# PIRSN_v2.net
KiCad netlist of a schematic drawn in EAGLE
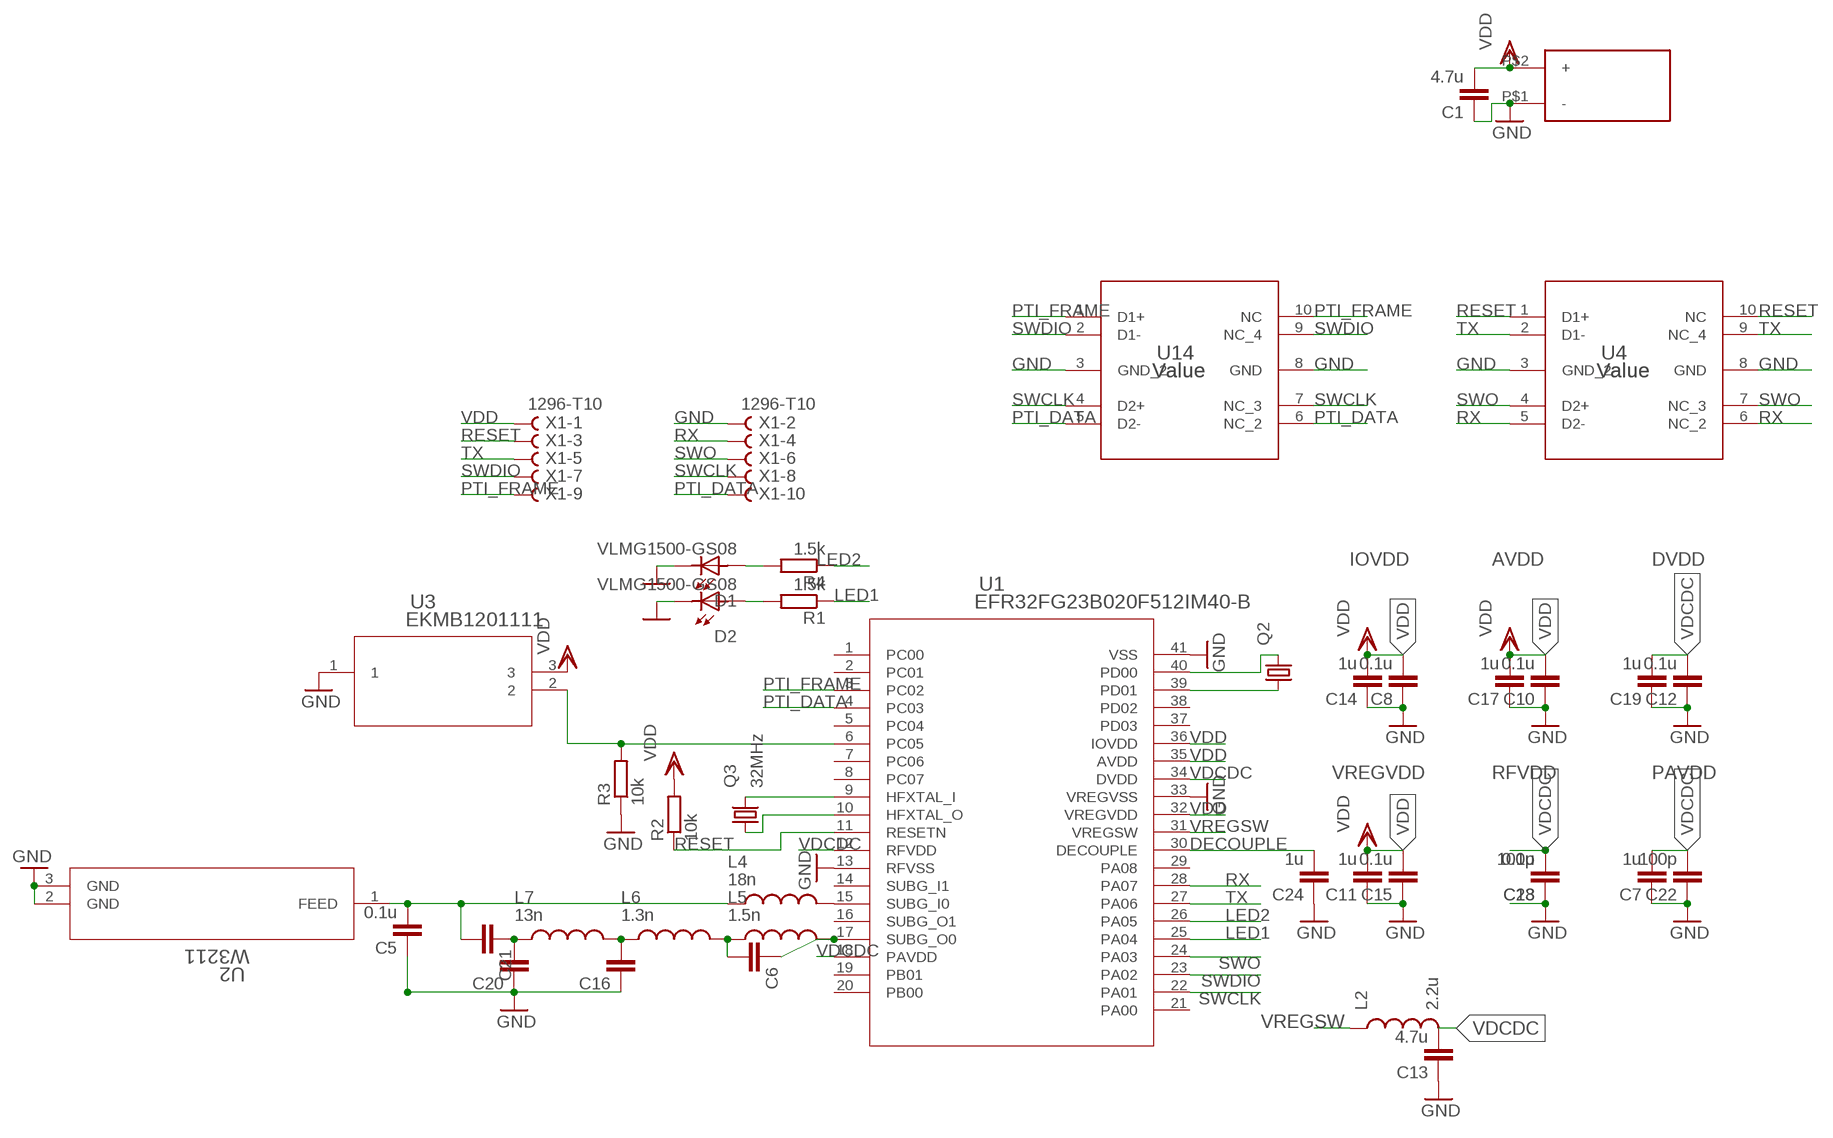
[diagram p0: schematic, sheet 1]

(export (version "E")
  (design (tool "Eeschema 10.0.6"))
  (components
    (comp (ref "C1")
      (value "4.7u")
      (footprint "eagle-import:C0603R")
      (libsource (lib "eagle-import") (part "CC0603R"))
    )
    (comp (ref "C5")
      (value "0.1u")
      (footprint "eagle-import:C0402")
      (libsource (lib "eagle-import") (part "CC0402"))
    )
    (comp (ref "C6")
      (value "1.9p")
      (footprint "eagle-import:C0402")
      (libsource (lib "eagle-import") (part "CC0402"))
    )
    (comp (ref "C7")
      (value "1u")
      (footprint "eagle-import:C0402")
      (libsource (lib "eagle-import") (part "CC0402"))
    )
    (comp (ref "C8")
      (value "0.1u")
      (footprint "eagle-import:C0402")
      (libsource (lib "eagle-import") (part "CC0402"))
    )
    (comp (ref "C10")
      (value "0.1u")
      (footprint "eagle-import:C0402")
      (libsource (lib "eagle-import") (part "CC0402"))
    )
    (comp (ref "C11")
      (value "1u")
      (footprint "eagle-import:C0402")
      (libsource (lib "eagle-import") (part "CC0402"))
    )
    (comp (ref "C12")
      (value "0.1u")
      (footprint "eagle-import:C0402")
      (libsource (lib "eagle-import") (part "CC0402"))
    )
    (comp (ref "C13")
      (value "4.7u")
      (footprint "eagle-import:C0603R")
      (libsource (lib "eagle-import") (part "CC0603R"))
    )
    (comp (ref "C14")
      (value "1u")
      (footprint "eagle-import:C0402")
      (libsource (lib "eagle-import") (part "CC0402"))
    )
    (comp (ref "C15")
      (value "0.1u")
      (footprint "eagle-import:C0402")
      (libsource (lib "eagle-import") (part "CC0402"))
    )
    (comp (ref "C16")
      (value "7.2p")
      (footprint "eagle-import:C0402")
      (libsource (lib "eagle-import") (part "CC0402"))
    )
    (comp (ref "C17")
      (value "1u")
      (footprint "eagle-import:C0402")
      (libsource (lib "eagle-import") (part "CC0402"))
    )
    (comp (ref "C18")
      (value "0.1u")
      (footprint "eagle-import:C0402")
      (libsource (lib "eagle-import") (part "CC0402"))
    )
    (comp (ref "C19")
      (value "1u")
      (footprint "eagle-import:C0402")
      (libsource (lib "eagle-import") (part "CC0402"))
    )
    (comp (ref "C20")
      (value "1.3p")
      (footprint "eagle-import:C0402")
      (libsource (lib "eagle-import") (part "CC0402"))
    )
    (comp (ref "C21")
      (value "220p")
      (footprint "eagle-import:C0402")
      (libsource (lib "eagle-import") (part "CC0402"))
    )
    (comp (ref "C22")
      (value "100p")
      (footprint "eagle-import:C0402")
      (libsource (lib "eagle-import") (part "CC0402"))
    )
    (comp (ref "C23")
      (value "100p")
      (footprint "eagle-import:C0402")
      (libsource (lib "eagle-import") (part "CC0402"))
    )
    (comp (ref "C24")
      (value "1u")
      (footprint "eagle-import:C0402")
      (libsource (lib "eagle-import") (part "CC0402"))
    )
    (comp (ref "D1")
      (value "VLMG1500-GS08")
      (footprint "eagle-import:LEDC1005X35N")
      (fields (field (name "MF") "Vishay"))
      (libsource (lib "eagle-import") (part "VLMG1500-GS08"))
    )
    (comp (ref "D2")
      (value "VLMG1500-GS08")
      (footprint "eagle-import:LEDC1005X35N")
      (fields (field (name "MF") "Vishay"))
      (libsource (lib "eagle-import") (part "VLMG1500-GS08"))
    )
    (comp (ref "L2")
      (value "2.2u")
      (footprint "eagle-import:L0603")
      (libsource (lib "eagle-import") (part "INDUCTOR"))
    )
    (comp (ref "L4")
      (value "18n")
      (footprint "eagle-import:INDC0402X26N")
      (fields (field (name "MF") "TDK") (field (name "MP") "MHQ0402P7N5JT000"))
      (libsource (lib "eagle-import") (part "MHQ0402P7N5JT000"))
    )
    (comp (ref "L5")
      (value "1.5n")
      (footprint "eagle-import:INDC0402X26N")
      (fields (field (name "MF") "TDK") (field (name "MP") "MHQ0402P7N5JT000"))
      (libsource (lib "eagle-import") (part "MHQ0402P7N5JT000"))
    )
    (comp (ref "L6")
      (value "1.3n")
      (footprint "eagle-import:INDC0402X26N")
      (fields (field (name "MF") "TDK") (field (name "MP") "MHQ0402P7N5JT000"))
      (libsource (lib "eagle-import") (part "MHQ0402P7N5JT000"))
    )
    (comp (ref "L7")
      (value "13n")
      (footprint "eagle-import:INDC0402X26N")
      (fields (field (name "MF") "TDK") (field (name "MP") "MHQ0402P7N5JT000"))
      (libsource (lib "eagle-import") (part "MHQ0402P7N5JT000"))
    )
    (comp (ref "Q2")
      (value "KX-327-RT")
      (footprint "eagle-import:2.0X1.2")
      (libsource (lib "eagle-import") (part "KX-327-RT"))
    )
    (comp (ref "Q3")
      (value "32MHz")
      (footprint "eagle-import:2.0X1.6_KX-5")
      (libsource (lib "eagle-import") (part "KX-5"))
    )
    (comp (ref "R1")
      (value "1.5k")
      (footprint "eagle-import:R0402")
      (libsource (lib "eagle-import") (part "RR0402"))
    )
    (comp (ref "R2")
      (value "10k")
      (footprint "eagle-import:R0402")
      (libsource (lib "eagle-import") (part "RR0402"))
    )
    (comp (ref "R3")
      (value "10k")
      (footprint "eagle-import:R0402")
      (libsource (lib "eagle-import") (part "RR0402"))
    )
    (comp (ref "R4")
      (value "1.5k")
      (footprint "eagle-import:R0402")
      (libsource (lib "eagle-import") (part "RR0402"))
    )
    (comp (ref "U$2")
      (value "BS-24R")
      (footprint "eagle-import:BS-24")
      (libsource (lib "eagle-import") (part "BS-24R"))
    )
    (comp (ref "U1")
      (value "EFR32FG23B020F512IM40-B")
      (footprint "eagle-import:QFN_40_SIL")
      (fields (field (name "COPYRIGHT") "Copyright (C) 2022 Ultra Librarian. All rights reserved."))
      (libsource (lib "eagle-import") (part "EFR32FG23B020F512IM40-B"))
    )
    (comp (ref "U2")
      (value "W3211")
      (footprint "eagle-import:CHIP_3211_PUL")
      (fields (field (name "COPYRIGHT") "Copyright (C) 2022 Ultra Librarian. All rights reserved."))
      (libsource (lib "eagle-import") (part "W3211"))
    )
    (comp (ref "U3")
      (value "EKMB1201111")
      (footprint "eagle-import:SENSOR_B1201111_PAN")
      (fields (field (name "COPYRIGHT") "Copyright (C) 2022 Ultra Librarian. All rights reserved."))
      (libsource (lib "eagle-import") (part "EKMB1201111"))
    )
    (comp (ref "U4")
      (value "Value")
      (footprint "eagle-import:DQA0010A")
      (fields (field (name "MANUFACTURER") "Texas Instruments") (field (name "PARTNUMBER") "ESD204DQAR"))
      (libsource (lib "eagle-import") (part "ESD204DQAR"))
    )
    (comp (ref "U14")
      (value "Value")
      (footprint "eagle-import:DQA0010A")
      (fields (field (name "MANUFACTURER") "Texas Instruments") (field (name "PARTNUMBER") "ESD204DQAR"))
      (libsource (lib "eagle-import") (part "ESD204DQAR"))
    )
    (comp (ref "X1")
      (value "1296-T10")
      (footprint "eagle-import:1296-10")
      (libsource (lib "eagle-import") (part "1296-T10"))
    )
  )
  (nets
    (net (code "1") (name "/DECOUPLE") (class "Default")
      (node (ref "C24") (pin "2") (pinfunction "2_2") (pintype "passive"))
      (node (ref "U1") (pin "30") (pinfunction "DECOUPLE_30") (pintype "passive"))
    )
    (net (code "2") (name "/LED1") (class "Default")
      (node (ref "R1") (pin "1") (pinfunction "1_1") (pintype "passive"))
      (node (ref "U1") (pin "25") (pinfunction "PA04_25") (pintype "bidirectional"))
    )
    (net (code "3") (name "/LED2") (class "Default")
      (node (ref "R4") (pin "1") (pinfunction "1_1") (pintype "passive"))
      (node (ref "U1") (pin "26") (pinfunction "PA05_26") (pintype "bidirectional"))
    )
    (net (code "4") (name "/PTI_DATA") (class "Default")
      (node (ref "U1") (pin "4") (pinfunction "PC03_4") (pintype "bidirectional"))
      (node (ref "U14") (pin "5") (pinfunction "D2-_5") (pintype "bidirectional"))
      (node (ref "U14") (pin "6") (pinfunction "NC_2_6") (pintype "passive"))
      (node (ref "X1") (pin "10") (pinfunction "B_10") (pintype "passive"))
    )
    (net (code "5") (name "/PTI_FRAME") (class "Default")
      (node (ref "U1") (pin "3") (pinfunction "PC02_3") (pintype "bidirectional"))
      (node (ref "U14") (pin "1") (pinfunction "D1+_1") (pintype "bidirectional"))
      (node (ref "U14") (pin "10") (pinfunction "NC_10") (pintype "passive"))
      (node (ref "X1") (pin "9") (pinfunction "B_9") (pintype "passive"))
    )
    (net (code "6") (name "/RESET") (class "Default")
      (node (ref "R2") (pin "1") (pinfunction "1_1") (pintype "passive"))
      (node (ref "U1") (pin "11") (pinfunction "RESETN_11") (pintype "input"))
      (node (ref "U4") (pin "1") (pinfunction "D1+_1") (pintype "bidirectional"))
      (node (ref "U4") (pin "10") (pinfunction "NC_10") (pintype "passive"))
      (node (ref "X1") (pin "3") (pinfunction "B_3") (pintype "passive"))
    )
    (net (code "7") (name "/RX") (class "Default")
      (node (ref "U1") (pin "28") (pinfunction "PA07_28") (pintype "bidirectional"))
      (node (ref "U4") (pin "5") (pinfunction "D2-_5") (pintype "bidirectional"))
      (node (ref "U4") (pin "6") (pinfunction "NC_2_6") (pintype "passive"))
      (node (ref "X1") (pin "4") (pinfunction "B_4") (pintype "passive"))
    )
    (net (code "8") (name "/SWCLK") (class "Default")
      (node (ref "U1") (pin "22") (pinfunction "PA01_22") (pintype "bidirectional"))
      (node (ref "U14") (pin "4") (pinfunction "D2+_4") (pintype "bidirectional"))
      (node (ref "U14") (pin "7") (pinfunction "NC_3_7") (pintype "passive"))
      (node (ref "X1") (pin "8") (pinfunction "B_8") (pintype "passive"))
    )
    (net (code "9") (name "/SWDIO") (class "Default")
      (node (ref "U1") (pin "23") (pinfunction "PA02_23") (pintype "bidirectional"))
      (node (ref "U14") (pin "2") (pinfunction "D1-_2") (pintype "bidirectional"))
      (node (ref "U14") (pin "9") (pinfunction "NC_4_9") (pintype "passive"))
      (node (ref "X1") (pin "7") (pinfunction "B_7") (pintype "passive"))
    )
    (net (code "10") (name "/SWO") (class "Default")
      (node (ref "U1") (pin "24") (pinfunction "PA03_24") (pintype "bidirectional"))
      (node (ref "U4") (pin "4") (pinfunction "D2+_4") (pintype "bidirectional"))
      (node (ref "U4") (pin "7") (pinfunction "NC_3_7") (pintype "passive"))
      (node (ref "X1") (pin "6") (pinfunction "B_6") (pintype "passive"))
    )
    (net (code "11") (name "/TX") (class "Default")
      (node (ref "U1") (pin "27") (pinfunction "PA06_27") (pintype "bidirectional"))
      (node (ref "U4") (pin "2") (pinfunction "D1-_2") (pintype "bidirectional"))
      (node (ref "U4") (pin "9") (pinfunction "NC_4_9") (pintype "passive"))
      (node (ref "X1") (pin "5") (pinfunction "B_5") (pintype "passive"))
    )
    (net (code "12") (name "/VREGSW") (class "Default")
      (node (ref "L2") (pin "1") (pinfunction "1_1") (pintype "passive"))
      (node (ref "U1") (pin "31") (pinfunction "VREGSW_31") (pintype "power_in"))
    )
    (net (code "13") (name "GND") (class "Default")
      (node (ref "C1") (pin "1") (pinfunction "1_1") (pintype "passive"))
      (node (ref "C10") (pin "1") (pinfunction "1_1") (pintype "passive"))
      (node (ref "C11") (pin "1") (pinfunction "1_1") (pintype "passive"))
      (node (ref "C12") (pin "1") (pinfunction "1_1") (pintype "passive"))
      (node (ref "C13") (pin "1") (pinfunction "1_1") (pintype "passive"))
      (node (ref "C14") (pin "1") (pinfunction "1_1") (pintype "passive"))
      (node (ref "C15") (pin "1") (pinfunction "1_1") (pintype "passive"))
      (node (ref "C16") (pin "1") (pinfunction "1_1") (pintype "passive"))
      (node (ref "C17") (pin "1") (pinfunction "1_1") (pintype "passive"))
      (node (ref "C18") (pin "1") (pinfunction "1_1") (pintype "passive"))
      (node (ref "C19") (pin "1") (pinfunction "1_1") (pintype "passive"))
      (node (ref "C20") (pin "1") (pinfunction "1_1") (pintype "passive"))
      (node (ref "C22") (pin "1") (pinfunction "1_1") (pintype "passive"))
      (node (ref "C23") (pin "1") (pinfunction "1_1") (pintype "passive"))
      (node (ref "C24") (pin "1") (pinfunction "1_1") (pintype "passive"))
      (node (ref "C5") (pin "1") (pinfunction "1_1") (pintype "passive"))
      (node (ref "C7") (pin "1") (pinfunction "1_1") (pintype "passive"))
      (node (ref "C8") (pin "1") (pinfunction "1_1") (pintype "passive"))
      (node (ref "D1") (pin "2") (pinfunction "2_2") (pintype "passive"))
      (node (ref "D2") (pin "2") (pinfunction "2_2") (pintype "passive"))
      (node (ref "R3") (pin "1") (pinfunction "1_1") (pintype "passive"))
      (node (ref "U$2") (pin "P$1") (pinfunction "-_P$1") (pintype "bidirectional"))
      (node (ref "U1") (pin "13") (pinfunction "RFVSS_13") (pintype "power_in"))
      (node (ref "U1") (pin "33") (pinfunction "VREGVSS_33") (pintype "power_in"))
      (node (ref "U1") (pin "41") (pinfunction "VSS_41") (pintype "power_in"))
      (node (ref "U14") (pin "3") (pinfunction "GND_2_3") (pintype "power_in"))
      (node (ref "U14") (pin "8") (pinfunction "GND_8") (pintype "power_in"))
      (node (ref "U2") (pin "2") (pinfunction "GND_2") (pintype "passive"))
      (node (ref "U2") (pin "3") (pinfunction "GND_3") (pintype "passive"))
      (node (ref "U3") (pin "1") (pinfunction "1_1") (pintype "passive"))
      (node (ref "U4") (pin "3") (pinfunction "GND_2_3") (pintype "power_in"))
      (node (ref "U4") (pin "8") (pinfunction "GND_8") (pintype "power_in"))
      (node (ref "X1") (pin "2") (pinfunction "B_2") (pintype "passive"))
    )
    (net (code "14") (name "Net-(C6-Pad2)") (class "Default")
      (node (ref "C6") (pin "2") (pinfunction "2_2") (pintype "passive"))
      (node (ref "L5") (pin "1") (pinfunction "1_1") (pintype "passive"))
      (node (ref "L6") (pin "2") (pinfunction "2_2") (pintype "passive"))
    )
    (net (code "15") (name "Net-(C16-Pad2)") (class "Default")
      (node (ref "C16") (pin "2") (pinfunction "2_2") (pintype "passive"))
      (node (ref "L6") (pin "1") (pinfunction "1_1") (pintype "passive"))
      (node (ref "L7") (pin "2") (pinfunction "2_2") (pintype "passive"))
    )
    (net (code "16") (name "Net-(C20-Pad2)") (class "Default")
      (node (ref "C20") (pin "2") (pinfunction "2_2") (pintype "passive"))
      (node (ref "C21") (pin "1") (pinfunction "1_1") (pintype "passive"))
      (node (ref "L7") (pin "1") (pinfunction "1_1") (pintype "passive"))
    )
    (net (code "17") (name "Net-(D1-Pad1)") (class "Default")
      (node (ref "D1") (pin "1") (pinfunction "1_1") (pintype "passive"))
      (node (ref "R4") (pin "2") (pinfunction "2_2") (pintype "passive"))
    )
    (net (code "18") (name "Net-(D2-Pad1)") (class "Default")
      (node (ref "D2") (pin "1") (pinfunction "1_1") (pintype "passive"))
      (node (ref "R1") (pin "2") (pinfunction "2_2") (pintype "passive"))
    )
    (net (code "19") (name "Net-(Q3-2)") (class "Default")
      (node (ref "Q3") (pin "3") (pinfunction "2_3") (pintype "passive"))
      (node (ref "U1") (pin "9") (pinfunction "HFXTAL_I_9") (pintype "input"))
    )
    (net (code "20") (name "Net-(U1-HFXTAL_O)") (class "Default")
      (node (ref "Q3") (pin "1") (pinfunction "1_1") (pintype "passive"))
      (node (ref "U1") (pin "10") (pinfunction "HFXTAL_O_10") (pintype "output"))
    )
    (net (code "21") (name "Net-(U1-PC05)") (class "Default")
      (node (ref "R3") (pin "2") (pinfunction "2_2") (pintype "passive"))
      (node (ref "U1") (pin "6") (pinfunction "PC05_6") (pintype "bidirectional"))
      (node (ref "U3") (pin "2") (pinfunction "2_2") (pintype "passive"))
    )
    (net (code "22") (name "Net-(U1-PD00)") (class "Default")
      (node (ref "Q2") (pin "2") (pinfunction "2_2") (pintype "passive"))
      (node (ref "U1") (pin "40") (pinfunction "PD00_40") (pintype "bidirectional"))
    )
    (net (code "23") (name "Net-(U1-PD01)") (class "Default")
      (node (ref "Q2") (pin "1") (pinfunction "1_1") (pintype "passive"))
      (node (ref "U1") (pin "39") (pinfunction "PD01_39") (pintype "bidirectional"))
    )
    (net (code "24") (name "Net-(U1-SUBG_I0)") (class "Default")
      (node (ref "L4") (pin "2") (pinfunction "2_2") (pintype "passive"))
      (node (ref "U1") (pin "15") (pinfunction "SUBG_I0_15") (pintype "input"))
    )
    (net (code "25") (name "Net-(U1-SUBG_O0)") (class "Default")
      (node (ref "C6") (pin "1") (pinfunction "1_1") (pintype "passive"))
      (node (ref "L5") (pin "2") (pinfunction "2_2") (pintype "passive"))
      (node (ref "U1") (pin "17") (pinfunction "SUBG_O0_17") (pintype "output"))
    )
    (net (code "26") (name "Net-(U2-FEED)") (class "Default")
      (node (ref "C21") (pin "2") (pinfunction "2_2") (pintype "passive"))
      (node (ref "C5") (pin "2") (pinfunction "2_2") (pintype "passive"))
      (node (ref "L4") (pin "1") (pinfunction "1_1") (pintype "passive"))
      (node (ref "U2") (pin "1") (pinfunction "FEED_1") (pintype "passive"))
    )
    (net (code "27") (name "VDCDC") (class "Default")
      (node (ref "C12") (pin "2") (pinfunction "2_2") (pintype "passive"))
      (node (ref "C13") (pin "2") (pinfunction "2_2") (pintype "passive"))
      (node (ref "C18") (pin "2") (pinfunction "2_2") (pintype "passive"))
      (node (ref "C19") (pin "2") (pinfunction "2_2") (pintype "passive"))
      (node (ref "C22") (pin "2") (pinfunction "2_2") (pintype "passive"))
      (node (ref "C23") (pin "2") (pinfunction "2_2") (pintype "passive"))
      (node (ref "C7") (pin "2") (pinfunction "2_2") (pintype "passive"))
      (node (ref "L2") (pin "2") (pinfunction "2_2") (pintype "passive"))
      (node (ref "U1") (pin "12") (pinfunction "RFVDD_12") (pintype "power_in"))
      (node (ref "U1") (pin "18") (pinfunction "PAVDD_18") (pintype "power_in"))
      (node (ref "U1") (pin "34") (pinfunction "DVDD_34") (pintype "power_in"))
    )
    (net (code "28") (name "VDD") (class "Default")
      (node (ref "C1") (pin "2") (pinfunction "2_2") (pintype "passive"))
      (node (ref "C10") (pin "2") (pinfunction "2_2") (pintype "passive"))
      (node (ref "C11") (pin "2") (pinfunction "2_2") (pintype "passive"))
      (node (ref "C14") (pin "2") (pinfunction "2_2") (pintype "passive"))
      (node (ref "C15") (pin "2") (pinfunction "2_2") (pintype "passive"))
      (node (ref "C17") (pin "2") (pinfunction "2_2") (pintype "passive"))
      (node (ref "C8") (pin "2") (pinfunction "2_2") (pintype "passive"))
      (node (ref "R2") (pin "2") (pinfunction "2_2") (pintype "passive"))
      (node (ref "U$2") (pin "P$2") (pinfunction "+_P$2") (pintype "bidirectional"))
      (node (ref "U1") (pin "32") (pinfunction "VREGVDD_32") (pintype "power_in"))
      (node (ref "U1") (pin "35") (pinfunction "AVDD_35") (pintype "power_in"))
      (node (ref "U1") (pin "36") (pinfunction "IOVDD_36") (pintype "power_in"))
      (node (ref "U3") (pin "3") (pinfunction "3_3") (pintype "passive"))
      (node (ref "X1") (pin "1") (pinfunction "B_1") (pintype "passive"))
    )
    (net (code "29") (name "unconnected-(U1-PA00-Pad21)") (class "Default")
      (node (ref "U1") (pin "21") (pinfunction "PA00_21") (pintype "bidirectional"))
    )
    (net (code "30") (name "unconnected-(U1-PA08-Pad29)") (class "Default")
      (node (ref "U1") (pin "29") (pinfunction "PA08_29") (pintype "bidirectional"))
    )
    (net (code "31") (name "unconnected-(U1-PB00-Pad20)") (class "Default")
      (node (ref "U1") (pin "20") (pinfunction "PB00_20") (pintype "bidirectional"))
    )
    (net (code "32") (name "unconnected-(U1-PB01-Pad19)") (class "Default")
      (node (ref "U1") (pin "19") (pinfunction "PB01_19") (pintype "bidirectional"))
    )
    (net (code "33") (name "unconnected-(U1-PC00-Pad1)") (class "Default")
      (node (ref "U1") (pin "1") (pinfunction "PC00_1") (pintype "bidirectional"))
    )
    (net (code "34") (name "unconnected-(U1-PC01-Pad2)") (class "Default")
      (node (ref "U1") (pin "2") (pinfunction "PC01_2") (pintype "bidirectional"))
    )
    (net (code "35") (name "unconnected-(U1-PC04-Pad5)") (class "Default")
      (node (ref "U1") (pin "5") (pinfunction "PC04_5") (pintype "bidirectional"))
    )
    (net (code "36") (name "unconnected-(U1-PC06-Pad7)") (class "Default")
      (node (ref "U1") (pin "7") (pinfunction "PC06_7") (pintype "bidirectional"))
    )
    (net (code "37") (name "unconnected-(U1-PC07-Pad8)") (class "Default")
      (node (ref "U1") (pin "8") (pinfunction "PC07_8") (pintype "bidirectional"))
    )
    (net (code "38") (name "unconnected-(U1-PD02-Pad38)") (class "Default")
      (node (ref "U1") (pin "38") (pinfunction "PD02_38") (pintype "bidirectional"))
    )
    (net (code "39") (name "unconnected-(U1-PD03-Pad37)") (class "Default")
      (node (ref "U1") (pin "37") (pinfunction "PD03_37") (pintype "bidirectional"))
    )
    (net (code "40") (name "unconnected-(U1-SUBG_I1-Pad14)") (class "Default")
      (node (ref "U1") (pin "14") (pinfunction "SUBG_I1_14") (pintype "input"))
    )
    (net (code "41") (name "unconnected-(U1-SUBG_O1-Pad16)") (class "Default")
      (node (ref "U1") (pin "16") (pinfunction "SUBG_O1_16") (pintype "output"))
    )
  )
)
